# SCH_MAN4HEALTH_2023-02-25.net
KiCad netlist of a schematic drawn in EasyEDA
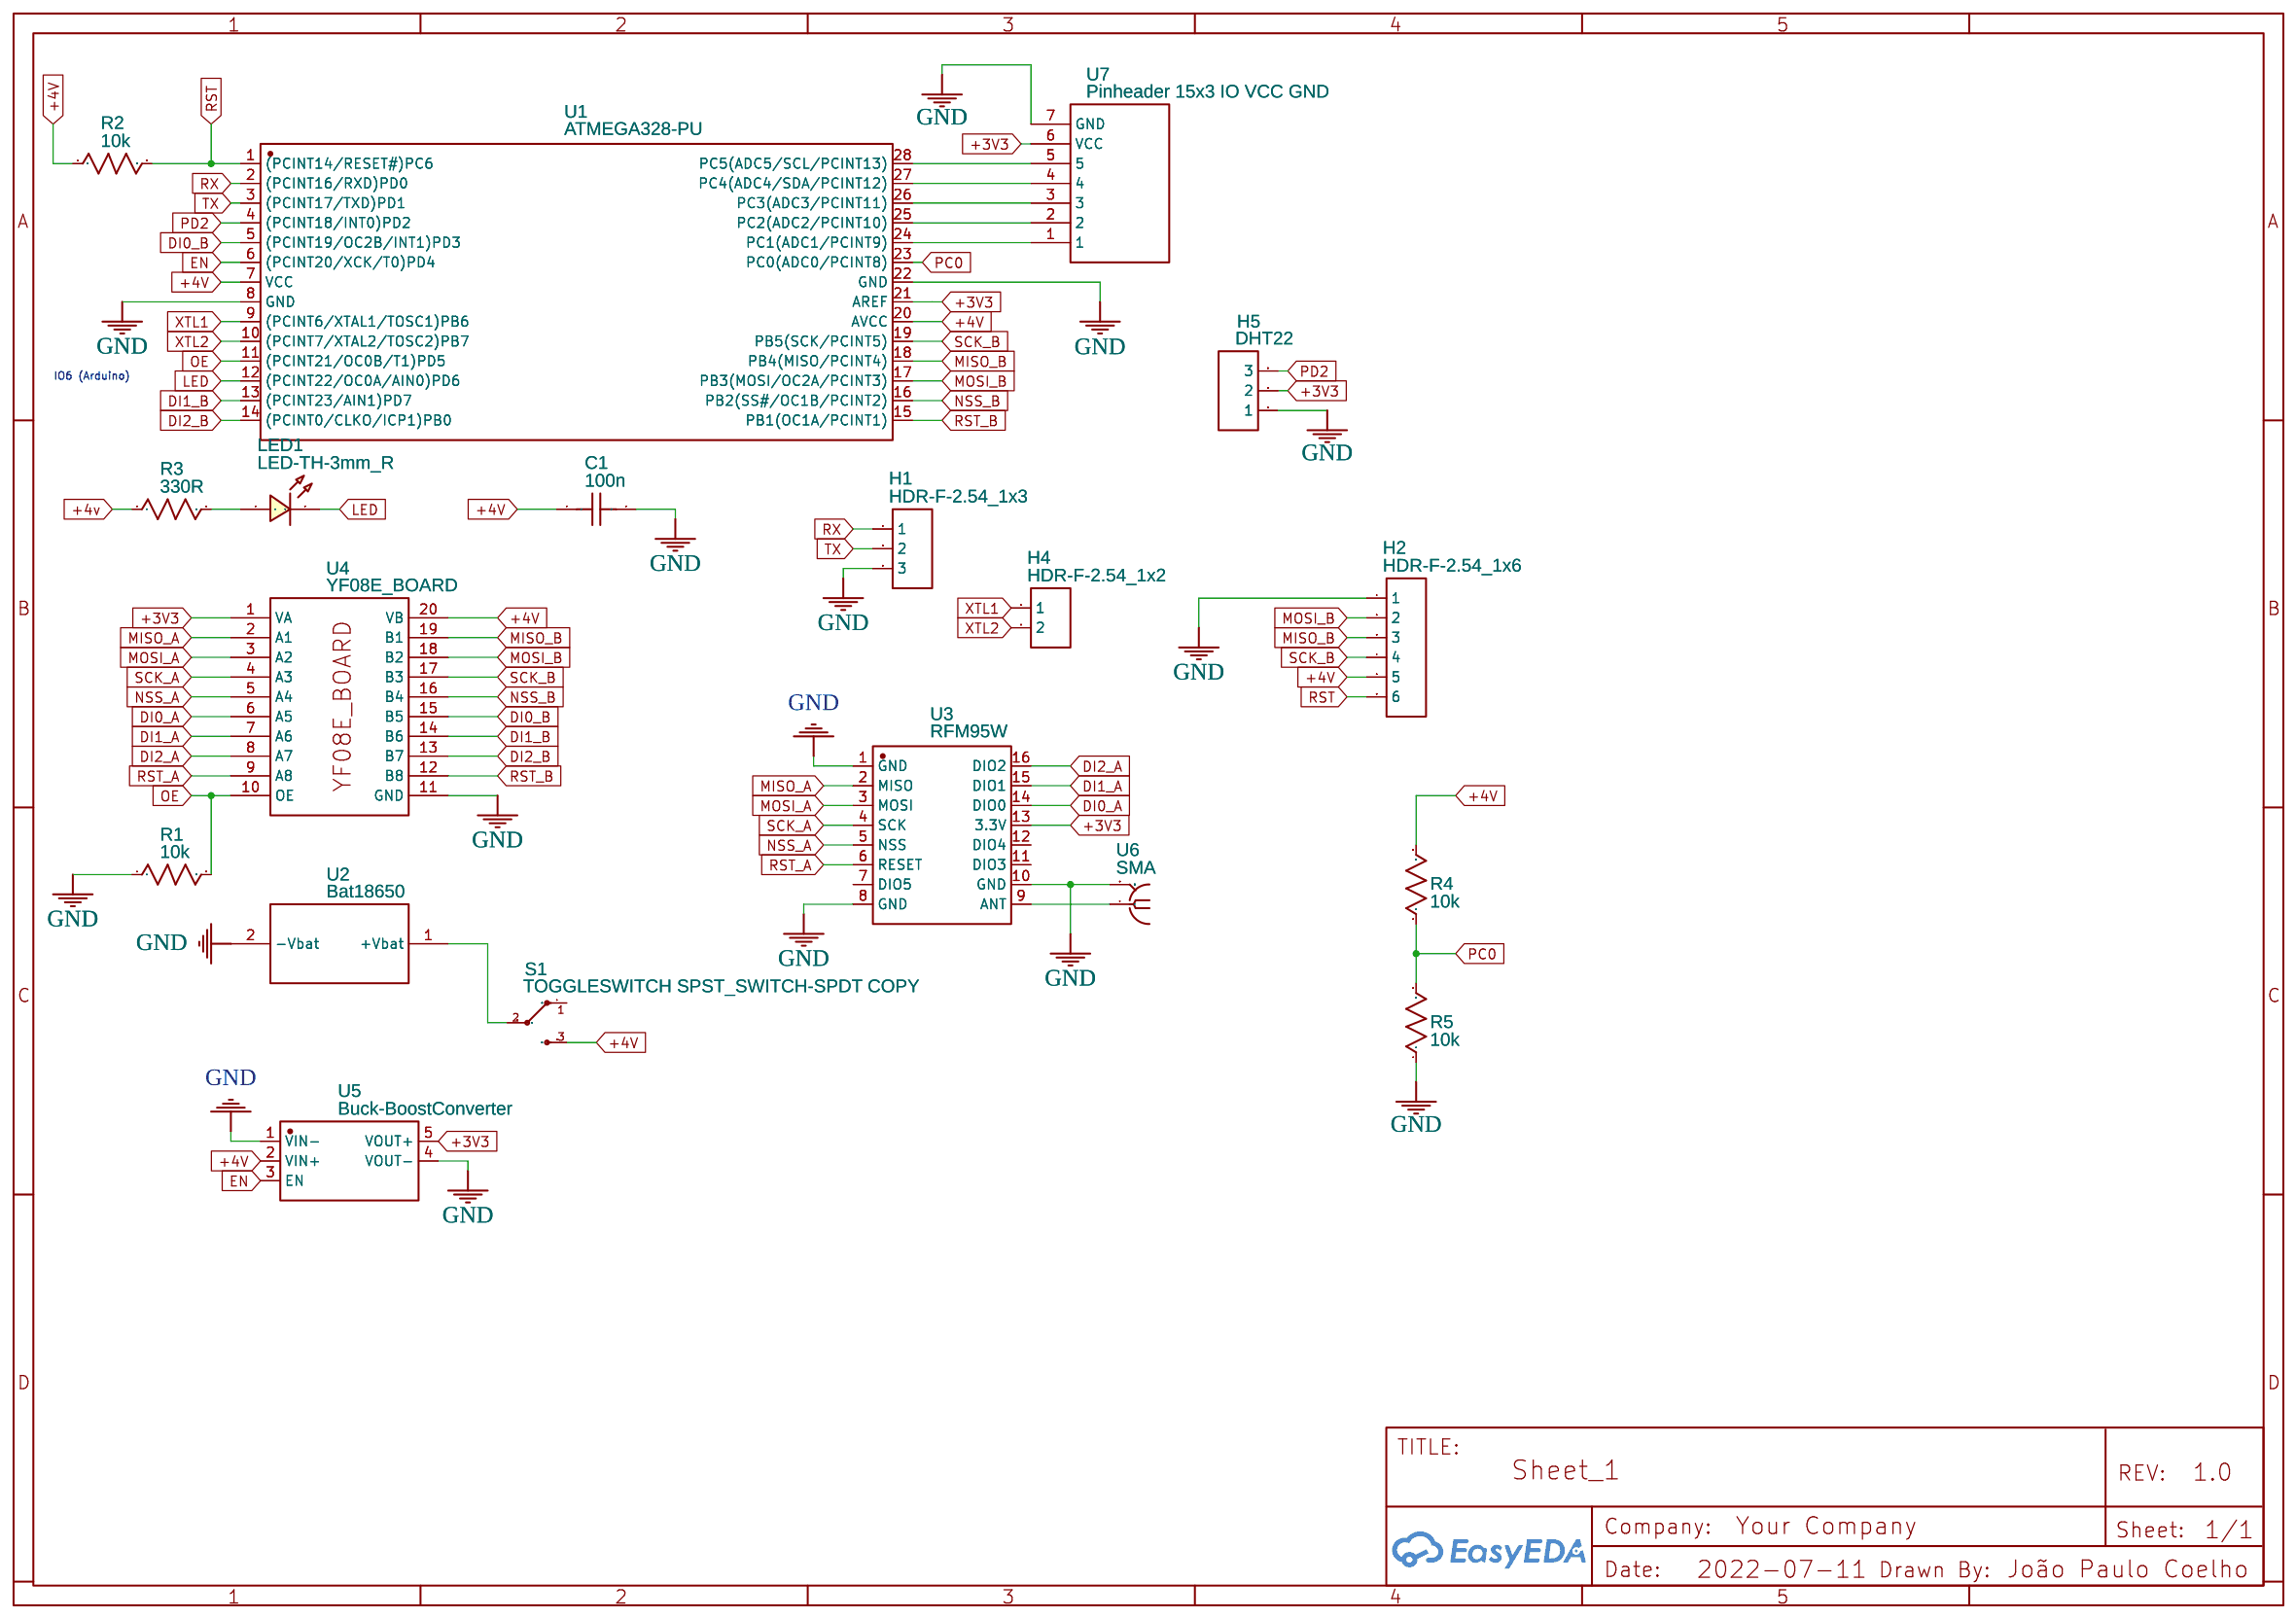
[diagram p0: schematic sheet]

(export (version "E")
  (design (tool "Eeschema 10.0.6"))
  (components
    (comp (ref "C1") (value "100n") (libsource (lib "") (part "C_RAD-0.1_US")))
    (comp (ref "H1")
      (value "HDR-F-2.54_1x3")
      (fields (field (name "BOM_Supplier Part") "C146690"))
      (libsource (lib "") (part "HDR-F-2.54_1x3_1"))
    )
    (comp (ref "H2")
      (value "HDR-F-2.54_1x6")
      (fields (field (name "BOM_Supplier Part") "C40877"))
      (libsource (lib "") (part "HDR-F-2.54_1x6"))
    )
    (comp (ref "H4")
      (value "HDR-F-2.54_1x2")
      (fields (field (name "BOM_Supplier Part") "C49661"))
      (libsource (lib "") (part "HDR-F-2.54_1x2"))
    )
    (comp (ref "H5")
      (value "DHT22")
      (fields (field (name "BOM_Supplier Part") "C146690"))
      (libsource (lib "") (part "HDR-F-2.54_1x3"))
    )
    (comp (ref "LED1")
      (value "LED-TH-3mm_R")
      (fields
        (field (name "BOM_Manufacturer Part") "204-10SDRD/S530-A3-L")
        (field (name "BOM_Supplier Part") "C84774")
      )
      (libsource (lib "") (part "LED-TH-3mm_R"))
    )
    (comp (ref "R1") (value "10k") (libsource (lib "") (part "R_AXIAL-0.3_US")))
    (comp (ref "R2") (value "10k") (libsource (lib "") (part "R_AXIAL-0.3_US")))
    (comp (ref "R3") (value "330R") (libsource (lib "") (part "R_AXIAL-0.3_US")))
    (comp (ref "R4") (value "10k") (libsource (lib "") (part "R_0603_US")))
    (comp (ref "R5") (value "10k") (libsource (lib "") (part "R_0603_US")))
    (comp (ref "S1")
      (value "TOGGLESWITCH SPST_SWITCH-SPDT COPY")
      (libsource (lib "") (part "TOGGLESWITCH SPST_SWITCH-SPDT COPY"))
    )
    (comp (ref "U1")
      (value "ATMEGA328-PU")
      (fields (field (name "BOM_Supplier Part") "C613508"))
      (libsource (lib "") (part "ATMEGA328-PU"))
    )
    (comp (ref "U2") (value "Bat18650") (libsource (lib "") (part "Bat18650")))
    (comp (ref "U3")
      (value "RFM95W")
      (fields (field (name "BOM_Supplier Part") "C9900000484"))
      (libsource (lib "") (part "RFM95W"))
    )
    (comp (ref "U4") (value "YF08E_BOARD") (libsource (lib "") (part "YF08E_BOARD")))
    (comp (ref "U5")
      (value "Buck-BoostConverter")
      (fields (field (name "BOM_Manufacturer Part") "ME"))
      (libsource (lib "") (part "Buck-BoostConverter"))
    )
    (comp (ref "U6") (value "SMA") (libsource (lib "") (part "SMA")))
    (comp (ref "U7")
      (value "Pinheader 15x3 IO VCC GND")
      (libsource (lib "") (part "Pinheader 15x3 IO VCC GND"))
    )
  )
  (nets
    (net (code "1") (name "+3V3") (class "Default")
      (node (ref "H5") (pin "2") (pinfunction "2_2") (pintype "input"))
      (node (ref "U1") (pin "21") (pinfunction "AREF_21") (pintype "unspecified"))
      (node (ref "U3") (pin "13") (pinfunction "3.3V_13") (pintype "unspecified"))
      (node (ref "U4") (pin "1") (pinfunction "VA_1") (pintype "unspecified"))
      (node (ref "U5") (pin "5") (pinfunction "VOUT+_5") (pintype "unspecified"))
      (node (ref "U7") (pin "6") (pinfunction "VCC_6") (pintype "unspecified"))
    )
    (net (code "2") (name "+4V") (class "Default")
      (node (ref "C1") (pin "1") (pinfunction "1_1") (pintype "unspecified"))
      (node (ref "H2") (pin "5") (pinfunction "5_5") (pintype "input"))
      (node (ref "R2") (pin "1") (pinfunction "1_1") (pintype "unspecified"))
      (node (ref "R4") (pin "2") (pinfunction "2_2") (pintype "unspecified"))
      (node (ref "S1") (pin "3") (pinfunction "S_3") (pintype "unspecified"))
      (node (ref "U1") (pin "20") (pinfunction "AVCC_20") (pintype "unspecified"))
      (node (ref "U1") (pin "7") (pinfunction "VCC_7") (pintype "unspecified"))
      (node (ref "U4") (pin "20") (pinfunction "VB_20") (pintype "unspecified"))
      (node (ref "U5") (pin "2") (pinfunction "VIN+_2") (pintype "unspecified"))
    )
    (net (code "3") (name "+4v") (class "Default")
      (node (ref "R3") (pin "1") (pinfunction "1_1") (pintype "unspecified"))
    )
    (net (code "4") (name "DI0_A") (class "Default")
      (node (ref "U3") (pin "14") (pinfunction "DIO0_14") (pintype "unspecified"))
      (node (ref "U4") (pin "6") (pinfunction "A5_6") (pintype "unspecified"))
    )
    (net (code "5") (name "DI0_B") (class "Default")
      (node (ref "U1") (pin "5") (pinfunction "(PCINT19/OC2B/INT1)PD3_5") (pintype "unspecified"))
      (node (ref "U4") (pin "15") (pinfunction "B5_15") (pintype "unspecified"))
    )
    (net (code "6") (name "DI1_A") (class "Default")
      (node (ref "U3") (pin "15") (pinfunction "DIO1_15") (pintype "unspecified"))
      (node (ref "U4") (pin "7") (pinfunction "A6_7") (pintype "unspecified"))
    )
    (net (code "7") (name "DI1_B") (class "Default")
      (node (ref "U1") (pin "13") (pinfunction "(PCINT23/AIN1)PD7_13") (pintype "unspecified"))
      (node (ref "U4") (pin "14") (pinfunction "B6_14") (pintype "unspecified"))
    )
    (net (code "8") (name "DI2_A") (class "Default")
      (node (ref "U3") (pin "16") (pinfunction "DIO2_16") (pintype "unspecified"))
      (node (ref "U4") (pin "8") (pinfunction "A7_8") (pintype "unspecified"))
    )
    (net (code "9") (name "DI2_B") (class "Default")
      (node (ref "U1") (pin "14") (pinfunction "(PCINT0/CLKO/ICP1)PB0_14") (pintype "unspecified"))
      (node (ref "U4") (pin "13") (pinfunction "B7_13") (pintype "unspecified"))
    )
    (net (code "10") (name "EN") (class "Default")
      (node (ref "U1") (pin "6") (pinfunction "(PCINT20/XCK/T0)PD4_6") (pintype "unspecified"))
      (node (ref "U5") (pin "3") (pinfunction "EN_3") (pintype "unspecified"))
    )
    (net (code "11") (name "GND") (class "Default")
      (node (ref "C1") (pin "2") (pinfunction "2_2") (pintype "unspecified"))
      (node (ref "H1") (pin "3") (pinfunction "3_3") (pintype "input"))
      (node (ref "H2") (pin "1") (pinfunction "1_1") (pintype "input"))
      (node (ref "H5") (pin "1") (pinfunction "1_1") (pintype "input"))
      (node (ref "R1") (pin "1") (pinfunction "1_1") (pintype "unspecified"))
      (node (ref "R5") (pin "1") (pinfunction "1_1") (pintype "unspecified"))
      (node (ref "U1") (pin "22") (pinfunction "GND_22") (pintype "unspecified"))
      (node (ref "U1") (pin "8") (pinfunction "GND_8") (pintype "unspecified"))
      (node (ref "U2") (pin "2") (pinfunction "-Vbat_2") (pintype "unspecified"))
      (node (ref "U3") (pin "1") (pinfunction "GND_1") (pintype "unspecified"))
      (node (ref "U3") (pin "10") (pinfunction "GND_10") (pintype "unspecified"))
      (node (ref "U3") (pin "8") (pinfunction "GND_8") (pintype "unspecified"))
      (node (ref "U4") (pin "11") (pinfunction "GND_11") (pintype "unspecified"))
      (node (ref "U5") (pin "1") (pinfunction "VIN-_1") (pintype "unspecified"))
      (node (ref "U5") (pin "4") (pinfunction "VOUT-_4") (pintype "unspecified"))
      (node (ref "U6") (pin "2") (pinfunction "GND_2") (pintype "passive"))
      (node (ref "U7") (pin "7") (pinfunction "GND_7") (pintype "unspecified"))
    )
    (net (code "12") (name "LED") (class "Default")
      (node (ref "LED1") (pin "2") (pinfunction "2_2") (pintype "unspecified"))
      (node (ref "U1") (pin "12") (pinfunction "(PCINT22/OC0A/AIN0)PD6_12") (pintype "unspecified"))
    )
    (net (code "13") (name "MISO_A") (class "Default")
      (node (ref "U3") (pin "2") (pinfunction "MISO_2") (pintype "unspecified"))
      (node (ref "U4") (pin "2") (pinfunction "A1_2") (pintype "unspecified"))
    )
    (net (code "14") (name "MISO_B") (class "Default")
      (node (ref "H2") (pin "3") (pinfunction "3_3") (pintype "input"))
      (node (ref "U1") (pin "18") (pinfunction "PB4(MISO/PCINT4)_18") (pintype "unspecified"))
      (node (ref "U4") (pin "19") (pinfunction "B1_19") (pintype "unspecified"))
    )
    (net (code "15") (name "MOSI_A") (class "Default")
      (node (ref "U3") (pin "3") (pinfunction "MOSI_3") (pintype "unspecified"))
      (node (ref "U4") (pin "3") (pinfunction "A2_3") (pintype "unspecified"))
    )
    (net (code "16") (name "MOSI_B") (class "Default")
      (node (ref "H2") (pin "2") (pinfunction "2_2") (pintype "input"))
      (node (ref "U1") (pin "17") (pinfunction "PB3(MOSI/OC2A/PCINT3)_17") (pintype "unspecified"))
      (node (ref "U4") (pin "18") (pinfunction "B2_18") (pintype "unspecified"))
    )
    (net (code "17") (name "NSS_A") (class "Default")
      (node (ref "U3") (pin "5") (pinfunction "NSS_5") (pintype "unspecified"))
      (node (ref "U4") (pin "5") (pinfunction "A4_5") (pintype "unspecified"))
    )
    (net (code "18") (name "NSS_B") (class "Default")
      (node (ref "U1") (pin "16") (pinfunction "PB2(SS#/OC1B/PCINT2)_16") (pintype "unspecified"))
      (node (ref "U4") (pin "16") (pinfunction "B4_16") (pintype "unspecified"))
    )
    (net (code "19") (name "Net-(LED1-Pad1)") (class "Default")
      (node (ref "LED1") (pin "1") (pinfunction "1_1") (pintype "unspecified"))
      (node (ref "R3") (pin "2") (pinfunction "2_2") (pintype "unspecified"))
    )
    (net (code "20") (name "Net-(S1-P)") (class "Default")
      (node (ref "S1") (pin "2") (pinfunction "P_2") (pintype "unspecified"))
      (node (ref "U2") (pin "1") (pinfunction "+Vbat_1") (pintype "unspecified"))
    )
    (net (code "21") (name "Net-(U1-PC1(ADC1{slash}PCINT9))") (class "Default")
      (node (ref "U1") (pin "24") (pinfunction "PC1(ADC1/PCINT9)_24") (pintype "unspecified"))
      (node (ref "U7") (pin "1") (pinfunction "1_1") (pintype "unspecified"))
    )
    (net (code "22") (name "Net-(U1-PC2(ADC2{slash}PCINT10))") (class "Default")
      (node (ref "U1") (pin "25") (pinfunction "PC2(ADC2/PCINT10)_25") (pintype "unspecified"))
      (node (ref "U7") (pin "2") (pinfunction "2_2") (pintype "unspecified"))
    )
    (net (code "23") (name "Net-(U1-PC3(ADC3{slash}PCINT11))") (class "Default")
      (node (ref "U1") (pin "26") (pinfunction "PC3(ADC3/PCINT11)_26") (pintype "unspecified"))
      (node (ref "U7") (pin "3") (pinfunction "3_3") (pintype "unspecified"))
    )
    (net (code "24") (name "Net-(U1-PC4(ADC4{slash}SDA{slash}PCINT12))") (class "Default")
      (node (ref "U1") (pin "27") (pinfunction "PC4(ADC4/SDA/PCINT12)_27") (pintype "unspecified"))
      (node (ref "U7") (pin "4") (pinfunction "4_4") (pintype "unspecified"))
    )
    (net (code "25") (name "Net-(U1-PC5(ADC5{slash}SCL{slash}PCINT13))") (class "Default")
      (node (ref "U1") (pin "28") (pinfunction "PC5(ADC5/SCL/PCINT13)_28") (pintype "unspecified"))
      (node (ref "U7") (pin "5") (pinfunction "5_5") (pintype "unspecified"))
    )
    (net (code "26") (name "Net-(U3-ANT)") (class "Default")
      (node (ref "U3") (pin "9") (pinfunction "ANT_9") (pintype "unspecified"))
      (node (ref "U6") (pin "1") (pinfunction "1_1") (pintype "input"))
    )
    (net (code "27") (name "OE") (class "Default")
      (node (ref "R1") (pin "2") (pinfunction "2_2") (pintype "unspecified"))
      (node (ref "U1") (pin "11") (pinfunction "(PCINT21/OC0B/T1)PD5_11") (pintype "unspecified"))
      (node (ref "U4") (pin "10") (pinfunction "OE_10") (pintype "unspecified"))
    )
    (net (code "28") (name "PC0") (class "Default")
      (node (ref "R4") (pin "1") (pinfunction "1_1") (pintype "unspecified"))
      (node (ref "R5") (pin "2") (pinfunction "2_2") (pintype "unspecified"))
      (node (ref "U1") (pin "23") (pinfunction "PC0(ADC0/PCINT8)_23") (pintype "unspecified"))
    )
    (net (code "29") (name "PD2") (class "Default")
      (node (ref "H5") (pin "3") (pinfunction "3_3") (pintype "input"))
      (node (ref "U1") (pin "4") (pinfunction "(PCINT18/INT0)PD2_4") (pintype "unspecified"))
    )
    (net (code "30") (name "RST") (class "Default")
      (node (ref "H2") (pin "6") (pinfunction "6_6") (pintype "input"))
      (node (ref "R2") (pin "2") (pinfunction "2_2") (pintype "unspecified"))
      (node (ref "U1") (pin "1") (pinfunction "(PCINT14/RESET#)PC6_1") (pintype "unspecified"))
    )
    (net (code "31") (name "RST_A") (class "Default")
      (node (ref "U3") (pin "6") (pinfunction "RESET_6") (pintype "unspecified"))
      (node (ref "U4") (pin "9") (pinfunction "A8_9") (pintype "unspecified"))
    )
    (net (code "32") (name "RST_B") (class "Default")
      (node (ref "U1") (pin "15") (pinfunction "PB1(OC1A/PCINT1)_15") (pintype "unspecified"))
      (node (ref "U4") (pin "12") (pinfunction "B8_12") (pintype "unspecified"))
    )
    (net (code "33") (name "RX") (class "Default")
      (node (ref "H1") (pin "1") (pinfunction "1_1") (pintype "input"))
      (node (ref "U1") (pin "2") (pinfunction "(PCINT16/RXD)PD0_2") (pintype "unspecified"))
    )
    (net (code "34") (name "SCK_A") (class "Default")
      (node (ref "U3") (pin "4") (pinfunction "SCK_4") (pintype "unspecified"))
      (node (ref "U4") (pin "4") (pinfunction "A3_4") (pintype "unspecified"))
    )
    (net (code "35") (name "SCK_B") (class "Default")
      (node (ref "H2") (pin "4") (pinfunction "4_4") (pintype "input"))
      (node (ref "U1") (pin "19") (pinfunction "PB5(SCK/PCINT5)_19") (pintype "unspecified"))
      (node (ref "U4") (pin "17") (pinfunction "B3_17") (pintype "unspecified"))
    )
    (net (code "36") (name "TX") (class "Default")
      (node (ref "H1") (pin "2") (pinfunction "2_2") (pintype "input"))
      (node (ref "U1") (pin "3") (pinfunction "(PCINT17/TXD)PD1_3") (pintype "unspecified"))
    )
    (net (code "37") (name "XTL1") (class "Default")
      (node (ref "H4") (pin "1") (pinfunction "1_1") (pintype "input"))
      (node (ref "U1") (pin "9") (pinfunction "(PCINT6/XTAL1/TOSC1)PB6_9") (pintype "unspecified"))
    )
    (net (code "38") (name "XTL2") (class "Default")
      (node (ref "H4") (pin "2") (pinfunction "2_2") (pintype "input"))
      (node (ref "U1") (pin "10") (pinfunction "(PCINT7/XTAL2/TOSC2)PB7_10") (pintype "unspecified"))
    )
    (net (code "39") (name "unconnected-(S1-O-Pad1)") (class "Default")
      (node (ref "S1") (pin "1") (pinfunction "O_1") (pintype "unspecified"))
    )
    (net (code "40") (name "unconnected-(U3-DIO3-Pad11)") (class "Default")
      (node (ref "U3") (pin "11") (pinfunction "DIO3_11") (pintype "unspecified"))
    )
    (net (code "41") (name "unconnected-(U3-DIO4-Pad12)") (class "Default")
      (node (ref "U3") (pin "12") (pinfunction "DIO4_12") (pintype "unspecified"))
    )
    (net (code "42") (name "unconnected-(U3-DIO5-Pad7)") (class "Default")
      (node (ref "U3") (pin "7") (pinfunction "DIO5_7") (pintype "unspecified"))
    )
  )
)
